# mixer_headphone_amp.net
KiCad netlist of a schematic drawn in EAGLE
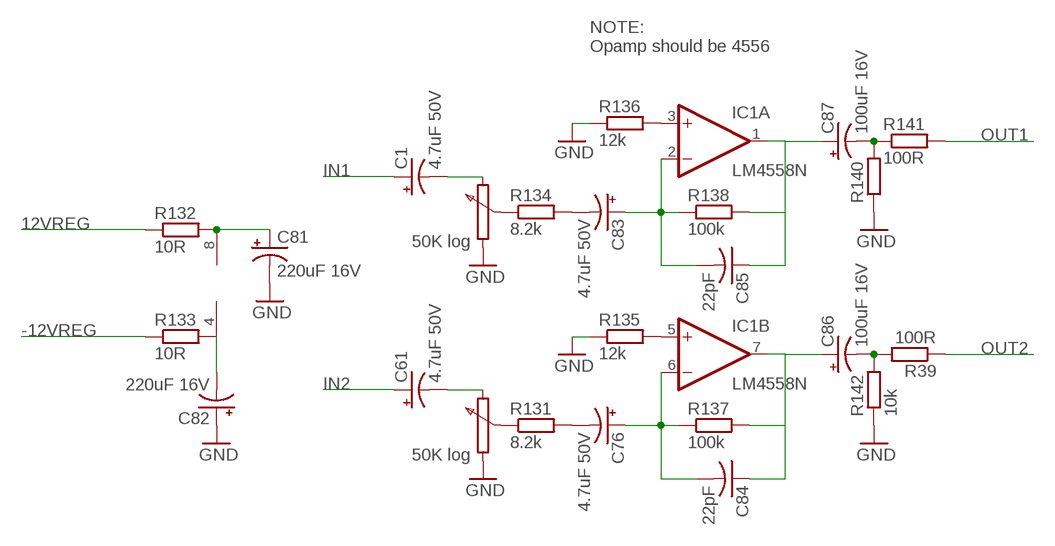
[diagram p0: schematic, sheet 1]

(export (version "E")
  (design (tool "Eeschema 10.0.6"))
  (components
    (comp (ref "C1")
      (value "4.7uF 50V")
      (footprint "eagle-import:E2,5-5")
      (libsource (lib "eagle-import") (part "CPOL-USE2.5-5"))
    )
    (comp (ref "C61")
      (value "4.7uF 50V")
      (footprint "eagle-import:E2,5-5")
      (libsource (lib "eagle-import") (part "CPOL-USE2.5-5"))
    )
    (comp (ref "C76")
      (value "4.7uF 50V")
      (footprint "eagle-import:E2,5-5")
      (libsource (lib "eagle-import") (part "CPOL-USE2.5-5"))
    )
    (comp (ref "C81")
      (value "220uF 16V")
      (footprint "eagle-import:E2,5-5")
      (libsource (lib "eagle-import") (part "CPOL-USE2.5-5"))
    )
    (comp (ref "C82")
      (value "220uF 16V")
      (footprint "eagle-import:E2,5-5")
      (libsource (lib "eagle-import") (part "CPOL-USE2.5-5"))
    )
    (comp (ref "C83")
      (value "4.7uF 50V")
      (footprint "eagle-import:E2,5-5")
      (libsource (lib "eagle-import") (part "CPOL-USE2.5-5"))
    )
    (comp (ref "C84")
      (value "22pF")
      (footprint "eagle-import:C025-025X050")
      (libsource (lib "eagle-import") (part "C-US025-025X050"))
    )
    (comp (ref "C85")
      (value "22pF")
      (footprint "eagle-import:C025-025X050")
      (libsource (lib "eagle-import") (part "C-US025-025X050"))
    )
    (comp (ref "C86")
      (value "100uF 16V")
      (footprint "eagle-import:E2,5-5")
      (libsource (lib "eagle-import") (part "CPOL-USE2.5-5"))
    )
    (comp (ref "C87")
      (value "100uF 16V")
      (footprint "eagle-import:E2,5-5")
      (libsource (lib "eagle-import") (part "CPOL-USE2.5-5"))
    )
    (comp (ref "IC1")
      (value "LM4558N")
      (footprint "eagle-import:DIL08")
      (libsource (lib "eagle-import") (part "4558NLM"))
    )
    (comp (ref "R39")
      (value "100R")
      (footprint "eagle-import:0204_7")
      (libsource (lib "eagle-import") (part "R-EU_0204/7"))
    )
    (comp (ref "R131")
      (value "8.2k")
      (footprint "eagle-import:0204_7")
      (libsource (lib "eagle-import") (part "R-EU_0204/7"))
    )
    (comp (ref "R132")
      (value "10R")
      (footprint "eagle-import:0204_7")
      (libsource (lib "eagle-import") (part "R-EU_0204/7"))
    )
    (comp (ref "R133")
      (value "10R")
      (footprint "eagle-import:0204_7")
      (libsource (lib "eagle-import") (part "R-EU_0204/7"))
    )
    (comp (ref "R134")
      (value "8.2k")
      (footprint "eagle-import:0204_7")
      (libsource (lib "eagle-import") (part "R-EU_0204/7"))
    )
    (comp (ref "R135")
      (value "12k")
      (footprint "eagle-import:0204_7")
      (libsource (lib "eagle-import") (part "R-EU_0204/7"))
    )
    (comp (ref "R136")
      (value "12k")
      (footprint "eagle-import:0204_7")
      (libsource (lib "eagle-import") (part "R-EU_0204/7"))
    )
    (comp (ref "R137")
      (value "100k")
      (footprint "eagle-import:0204_7")
      (libsource (lib "eagle-import") (part "R-EU_0204/7"))
    )
    (comp (ref "R138")
      (value "100k")
      (footprint "eagle-import:0204_7")
      (libsource (lib "eagle-import") (part "R-EU_0204/7"))
    )
    (comp (ref "R140")
      (value "R-EU_0204/7")
      (footprint "eagle-import:0204_7")
      (libsource (lib "eagle-import") (part "R-EU_0204/7"))
    )
    (comp (ref "R141")
      (value "100R")
      (footprint "eagle-import:0204_7")
      (libsource (lib "eagle-import") (part "R-EU_0204/7"))
    )
    (comp (ref "R142")
      (value "10k")
      (footprint "eagle-import:0204_7")
      (libsource (lib "eagle-import") (part "R-EU_0204/7"))
    )
  )
  (nets
    (net (code "1") (name "/-12VREG") (class "Default")
      (node (ref "R133") (pin "1") (pinfunction "1_1") (pintype "passive"))
    )
    (net (code "2") (name "/12VREG") (class "Default")
      (node (ref "R132") (pin "1") (pinfunction "1_1") (pintype "passive"))
    )
    (net (code "3") (name "/IN1") (class "Default")
      (node (ref "C1") (pin "+") (pinfunction "+_+") (pintype "passive"))
    )
    (net (code "4") (name "/IN2") (class "Default")
      (node (ref "C61") (pin "+") (pinfunction "+_+") (pintype "passive"))
    )
    (net (code "5") (name "/OUT1") (class "Default")
      (node (ref "R141") (pin "2") (pinfunction "2_2") (pintype "passive"))
    )
    (net (code "6") (name "/OUT2") (class "Default")
      (node (ref "R39") (pin "1") (pinfunction "1_1") (pintype "passive"))
    )
    (net (code "7") (name "GND") (class "Default")
      (node (ref "C81") (pin "-") (pinfunction "-_-") (pintype "passive"))
      (node (ref "C82") (pin "+") (pinfunction "+_+") (pintype "passive"))
      (node (ref "R135") (pin "1") (pinfunction "1_1") (pintype "passive"))
      (node (ref "R136") (pin "1") (pinfunction "1_1") (pintype "passive"))
      (node (ref "R140") (pin "1") (pinfunction "1_1") (pintype "passive"))
      (node (ref "R142") (pin "1") (pinfunction "1_1") (pintype "passive"))
    )
    (net (code "8") (name "Net-(C76-Pad-)") (class "Default")
      (node (ref "C76") (pin "-") (pinfunction "-_-") (pintype "passive"))
      (node (ref "R131") (pin "2") (pinfunction "2_2") (pintype "passive"))
    )
    (net (code "9") (name "Net-(C83-Pad-)") (class "Default")
      (node (ref "C83") (pin "-") (pinfunction "-_-") (pintype "passive"))
      (node (ref "R134") (pin "2") (pinfunction "2_2") (pintype "passive"))
    )
    (net (code "10") (name "Net-(C86-Pad-)") (class "Default")
      (node (ref "C86") (pin "-") (pinfunction "-_-") (pintype "passive"))
      (node (ref "R142") (pin "2") (pinfunction "2_2") (pintype "passive"))
      (node (ref "R39") (pin "2") (pinfunction "2_2") (pintype "passive"))
    )
    (net (code "11") (name "Net-(C87-Pad-)") (class "Default")
      (node (ref "C87") (pin "-") (pinfunction "-_-") (pintype "passive"))
      (node (ref "R140") (pin "2") (pinfunction "2_2") (pintype "passive"))
      (node (ref "R141") (pin "1") (pinfunction "1_1") (pintype "passive"))
    )
    (net (code "12") (name "Net-(IC1A-+IN)") (class "Default")
      (node (ref "IC1") (pin "3") (pinfunction "+IN_3") (pintype "input"))
      (node (ref "R136") (pin "2") (pinfunction "2_2") (pintype "passive"))
    )
    (net (code "13") (name "Net-(IC1A--IN)") (class "Default")
      (node (ref "C83") (pin "+") (pinfunction "+_+") (pintype "passive"))
      (node (ref "C85") (pin "2") (pinfunction "2_2") (pintype "passive"))
      (node (ref "IC1") (pin "2") (pinfunction "-IN_2") (pintype "input"))
      (node (ref "R138") (pin "1") (pinfunction "1_1") (pintype "passive"))
    )
    (net (code "14") (name "Net-(IC1A-OUT)") (class "Default")
      (node (ref "C85") (pin "1") (pinfunction "1_1") (pintype "passive"))
      (node (ref "C87") (pin "+") (pinfunction "+_+") (pintype "passive"))
      (node (ref "IC1") (pin "1") (pinfunction "OUT_1") (pintype "output"))
      (node (ref "R138") (pin "2") (pinfunction "2_2") (pintype "passive"))
    )
    (net (code "15") (name "Net-(IC1B-+IN)") (class "Default")
      (node (ref "IC1") (pin "5") (pinfunction "+IN_5") (pintype "input"))
      (node (ref "R135") (pin "2") (pinfunction "2_2") (pintype "passive"))
    )
    (net (code "16") (name "Net-(IC1B--IN)") (class "Default")
      (node (ref "C76") (pin "+") (pinfunction "+_+") (pintype "passive"))
      (node (ref "C84") (pin "2") (pinfunction "2_2") (pintype "passive"))
      (node (ref "IC1") (pin "6") (pinfunction "-IN_6") (pintype "input"))
      (node (ref "R137") (pin "1") (pinfunction "1_1") (pintype "passive"))
    )
    (net (code "17") (name "Net-(IC1B-OUT)") (class "Default")
      (node (ref "C84") (pin "1") (pinfunction "1_1") (pintype "passive"))
      (node (ref "C86") (pin "+") (pinfunction "+_+") (pintype "passive"))
      (node (ref "IC1") (pin "7") (pinfunction "OUT_7") (pintype "output"))
      (node (ref "R137") (pin "2") (pinfunction "2_2") (pintype "passive"))
    )
    (net (code "18") (name "Net-(IC1C-V+)") (class "Default")
      (node (ref "C81") (pin "+") (pinfunction "+_+") (pintype "passive"))
      (node (ref "IC1") (pin "8") (pinfunction "V+_8") (pintype "power_in"))
      (node (ref "R132") (pin "2") (pinfunction "2_2") (pintype "passive"))
    )
    (net (code "19") (name "Net-(IC1C-V-)") (class "Default")
      (node (ref "C82") (pin "-") (pinfunction "-_-") (pintype "passive"))
      (node (ref "IC1") (pin "4") (pinfunction "V-_4") (pintype "power_in"))
      (node (ref "R133") (pin "2") (pinfunction "2_2") (pintype "passive"))
    )
    (net (code "20") (name "unconnected-(C1-Pad-)") (class "Default")
      (node (ref "C1") (pin "-") (pinfunction "-_-") (pintype "passive"))
    )
    (net (code "21") (name "unconnected-(C61-Pad-)") (class "Default")
      (node (ref "C61") (pin "-") (pinfunction "-_-") (pintype "passive"))
    )
    (net (code "22") (name "unconnected-(R131-Pad1)") (class "Default")
      (node (ref "R131") (pin "1") (pinfunction "1_1") (pintype "passive"))
    )
    (net (code "23") (name "unconnected-(R134-Pad1)") (class "Default")
      (node (ref "R134") (pin "1") (pinfunction "1_1") (pintype "passive"))
    )
  )
)
